# dcdc_0501.net
KiCad netlist of a schematic drawn in EAGLE
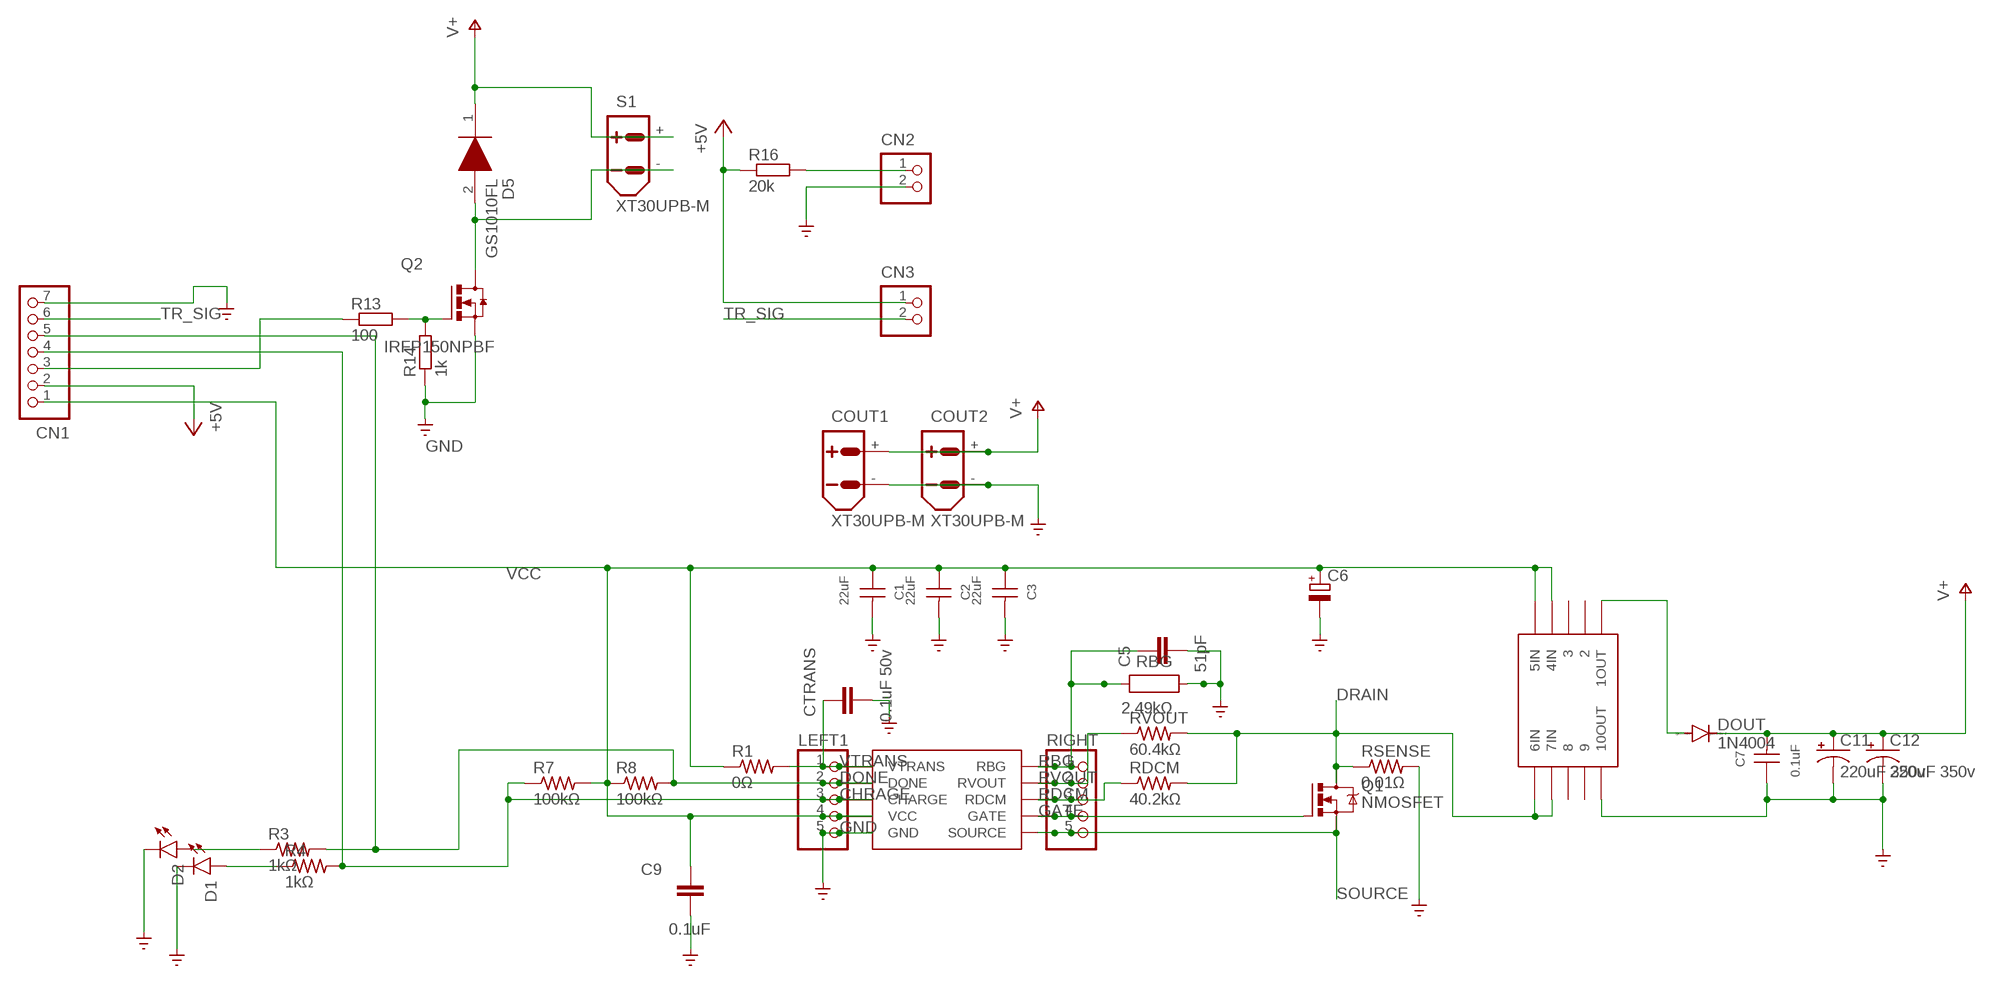
[diagram p0: schematic, sheet 1]

(export (version "E")
  (design (tool "Eeschema 10.0.6"))
  (components
    (comp (ref "C1")
      (value "22uF")
      (footprint "eagle-import:WCAP-CSGP_1210_H0.95")
      (libsource (lib "eagle-import") (part "WCAP-CSGP_1210_H0.95_25V(DC)_885012009002"))
    )
    (comp (ref "C2")
      (value "22uF")
      (footprint "eagle-import:WCAP-CSGP_1210_H0.95")
      (libsource (lib "eagle-import") (part "WCAP-CSGP_1210_H0.95_25V(DC)_885012009002"))
    )
    (comp (ref "C3")
      (value "22uF")
      (footprint "eagle-import:WCAP-CSGP_1210_H0.95")
      (libsource (lib "eagle-import") (part "WCAP-CSGP_1210_H0.95_25V(DC)_885012009002"))
    )
    (comp (ref "C5")
      (value "51pF")
      (footprint "eagle-import:CAP_0603")
      (fields
        (field (name "DIGIKEY_PART_NUMBER") "399-7814-2-ND")
        (field (name "MANUFACTURER") "KEMET")
        (field (name "MPN") "C0603C100C5GACTU")
        (field (name "CREATED_BY") "PCBLayout.com")
      )
      (libsource (lib "eagle-import") (part "C0603C100C5GACTU"))
    )
    (comp (ref "C6")
      (value "CPOL-EUTT2D6")
      (footprint "eagle-import:TT2D6")
      (libsource (lib "eagle-import") (part "CPOL-EUTT2D6"))
    )
    (comp (ref "C7")
      (value "0.1uF")
      (footprint "eagle-import:WCAP-CSGP_1812_H1.25")
      (libsource (lib "eagle-import") (part "WCAP-CSGP_1812_H1.25_16V(DC)_885012010001"))
    )
    (comp (ref "C9")
      (value "0.1uF")
      (footprint "eagle-import:CAP_0603")
      (fields
        (field (name "DIGIKEY_PART_NUMBER") "399-7814-2-ND")
        (field (name "MANUFACTURER") "KEMET")
        (field (name "MPN") "C0603C100C5GACTU")
        (field (name "CREATED_BY") "PCBLayout.com")
      )
      (libsource (lib "eagle-import") (part "C0603C100C5GACTU"))
    )
    (comp (ref "C11")
      (value "220uF 350v")
      (footprint "eagle-import:E7,5-18")
      (libsource (lib "eagle-import") (part "CAPACITOR-PE7.5-18"))
    )
    (comp (ref "C12")
      (value "220uF 350v")
      (footprint "eagle-import:E7,5-18")
      (libsource (lib "eagle-import") (part "CAPACITOR-PE7.5-18"))
    )
    (comp (ref "CN1")
      (value "B7B-XH-A")
      (footprint "eagle-import:B7B-XH-A")
      (libsource (lib "eagle-import") (part "B7B-XH-A"))
    )
    (comp (ref "CN2")
      (value "B2B-XH-A")
      (footprint "eagle-import:B2B-XH-A")
      (libsource (lib "eagle-import") (part "B2B-XH-A"))
    )
    (comp (ref "CN3")
      (value "B2B-XH-A")
      (footprint "eagle-import:B2B-XH-A")
      (libsource (lib "eagle-import") (part "B2B-XH-A"))
    )
    (comp (ref "COUT1")
      (value "XT30UPB-M")
      (footprint "eagle-import:XT30UPB-M")
      (libsource (lib "eagle-import") (part "XT30UPB-M"))
    )
    (comp (ref "COUT2")
      (value "XT30UPB-M")
      (footprint "eagle-import:XT30UPB-M")
      (libsource (lib "eagle-import") (part "XT30UPB-M"))
    )
    (comp (ref "CTRANS")
      (value "0.1uF 50v")
      (footprint "eagle-import:CAP_1206")
      (fields
        (field (name "DIGIKEY_PART_NUMBER") "GRM31CR60J107ME39L")
        (field (name "MANUFACTURER") "Murata Electronics North America")
        (field (name "CREATED_BY") "PCBLayout.com")
      )
      (libsource (lib "eagle-import") (part "GRM31CR60J107ME39L"))
    )
    (comp (ref "D1")
      (value "LED_RADIALWHITE")
      (footprint "eagle-import:LEDRD254W60D565H860B_W")
      (libsource (lib "eagle-import") (part "LED_RADIALWHITE"))
    )
    (comp (ref "D2")
      (value "LED_RADIALWHITE")
      (footprint "eagle-import:LEDRD254W60D565H860B_W")
      (libsource (lib "eagle-import") (part "LED_RADIALWHITE"))
    )
    (comp (ref "D5")
      (value "GS1010FL")
      (footprint "eagle-import:SODFL3618X110N")
      (libsource (lib "eagle-import") (part "GS1010FL"))
    )
    (comp (ref "DOUT")
      (value "1N4004")
      (footprint "eagle-import:DO41-10")
      (libsource (lib "eagle-import") (part "1N4004"))
    )
    (comp (ref "LEFT1")
      (value "PINHD-1X5")
      (footprint "eagle-import:1X05")
      (libsource (lib "eagle-import") (part "PINHD-1X5"))
    )
    (comp (ref "Q1")
      (value "NMOSFET")
      (footprint "eagle-import:TO220BV")
      (libsource (lib "eagle-import") (part "NMOSFET_TO220_"))
    )
    (comp (ref "Q2")
      (value "IRFP150NPBF")
      (footprint "eagle-import:TO-247AC")
      (fields
        (field (name "DIGIKEY_PART_NUMBER") "IRFP150NPBF-ND")
        (field (name "CREATED_BY") "PCBLayout.com")
      )
      (libsource (lib "eagle-import") (part "IRFP150NPBF"))
    )
    (comp (ref "R1")
      (value "0Ω")
      (footprint "eagle-import:M2012")
      (libsource (lib "eagle-import") (part "R-US_M2012"))
    )
    (comp (ref "R3")
      (value "1kΩ")
      (footprint "eagle-import:RES_0402")
      (fields
        (field (name "DIGIKEY_PART_NUMBER") "311-0.0JRTR-ND")
        (field (name "MANUFACTURER") "Yageo")
        (field (name "MPN") "RC0402JR-070RL")
        (field (name "CREATED_BY") "PCBLayout.com")
      )
      (libsource (lib "eagle-import") (part "RC0402JR-070RL"))
    )
    (comp (ref "R4")
      (value "1kΩ")
      (footprint "eagle-import:RES_0402")
      (fields
        (field (name "DIGIKEY_PART_NUMBER") "311-0.0JRTR-ND")
        (field (name "MANUFACTURER") "Yageo")
        (field (name "MPN") "RC0402JR-070RL")
        (field (name "CREATED_BY") "PCBLayout.com")
      )
      (libsource (lib "eagle-import") (part "RC0402JR-070RL"))
    )
    (comp (ref "R7")
      (value "100kΩ")
      (footprint "eagle-import:R1210")
      (libsource (lib "eagle-import") (part "R-US_R1210"))
    )
    (comp (ref "R8")
      (value "100kΩ")
      (footprint "eagle-import:R1210")
      (libsource (lib "eagle-import") (part "R-US_R1210"))
    )
    (comp (ref "R13")
      (value "100")
      (footprint "eagle-import:R0603")
      (libsource (lib "eagle-import") (part "R-EU_R0603"))
    )
    (comp (ref "R14")
      (value "1k")
      (footprint "eagle-import:R0603")
      (libsource (lib "eagle-import") (part "R-EU_R0603"))
    )
    (comp (ref "R16")
      (value "20k")
      (footprint "eagle-import:R0603")
      (libsource (lib "eagle-import") (part "R-EU_R0603"))
    )
    (comp (ref "RBG")
      (value "2.49kΩ")
      (footprint "eagle-import:WRIS_PSMC_2512_6.3X3.1X0.51X1.1(LXWXHXPW)")
      (libsource (lib "eagle-import") (part "WRIS-PSMC_2512_6.3X3.1X0.51X1.1_580070763005"))
    )
    (comp (ref "RDCM")
      (value "40.2kΩ")
      (footprint "eagle-import:RES_0805")
      (fields
        (field (name "DIGIKEY_PART_NUMBER") "541-0.0ATR-ND")
        (field (name "MANUFACTURER") "Vishay Dale")
        (field (name "MPN") "CRCW08050000Z0EA")
        (field (name "CREATED_BY") "PCBLayout.com")
      )
      (libsource (lib "eagle-import") (part "CRCW08050000Z0EA"))
    )
    (comp (ref "RIGHT")
      (value "PINHD-1X5")
      (footprint "eagle-import:1X05")
      (libsource (lib "eagle-import") (part "PINHD-1X5"))
    )
    (comp (ref "RSENSE")
      (value "0.01Ω")
      (footprint "eagle-import:RES_1206")
      (fields
        (field (name "DIGIKEY_PART_NUMBER") "WSLP-.05TR-ND")
        (field (name "MANUFACTURER") "Vishay Dale")
        (field (name "MPN") "WSLP1206R0500FEA")
        (field (name "CREATED_BY") "PCBLayout.com")
      )
      (libsource (lib "eagle-import") (part "WSLP1206R0500FEA"))
    )
    (comp (ref "RVOUT")
      (value "60.4kΩ")
      (footprint "eagle-import:RES_0805")
      (fields
        (field (name "DIGIKEY_PART_NUMBER") "541-0.0ATR-ND")
        (field (name "MANUFACTURER") "Vishay Dale")
        (field (name "MPN") "CRCW08050000Z0EA")
        (field (name "CREATED_BY") "PCBLayout.com")
      )
      (libsource (lib "eagle-import") (part "CRCW08050000Z0EA"))
    )
    (comp (ref "S1")
      (value "XT30UPB-M")
      (footprint "eagle-import:XT30UPB-M")
      (libsource (lib "eagle-import") (part "XT30UPB-M"))
    )
    (comp (ref "U$1")
      (value "LT3750_2")
      (footprint "eagle-import:LT3750_2")
      (libsource (lib "eagle-import") (part "LT3750_2"))
    )
    (comp (ref "U$2")
      (value "32052")
      (footprint "eagle-import:32052")
      (libsource (lib "eagle-import") (part "32052"))
    )
  )
  (nets
    (net (code "1") (name "+5V") (class "Default")
      (node (ref "CN1") (pin "2") (pinfunction "2_2") (pintype "passive"))
      (node (ref "CN3") (pin "1") (pinfunction "1_1") (pintype "passive"))
      (node (ref "R16") (pin "1") (pinfunction "1_1") (pintype "passive"))
    )
    (net (code "2") (name "/CHRAGE") (class "Default")
      (node (ref "CN1") (pin "4") (pinfunction "4_4") (pintype "passive"))
      (node (ref "LEFT1") (pin "3") (pinfunction "3_3") (pintype "passive"))
      (node (ref "R4") (pin "2") (pinfunction "2_2") (pintype "passive"))
      (node (ref "R7") (pin "1") (pinfunction "1_1") (pintype "passive"))
      (node (ref "U$1") (pin "CHARGE") (pinfunction "CHARGE_CHARGE") (pintype "bidirectional"))
    )
    (net (code "3") (name "/DONE") (class "Default")
      (node (ref "CN1") (pin "5") (pinfunction "5_5") (pintype "passive"))
      (node (ref "LEFT1") (pin "2") (pinfunction "2_2") (pintype "passive"))
      (node (ref "R3") (pin "2") (pinfunction "2_2") (pintype "passive"))
      (node (ref "R8") (pin "2") (pinfunction "2_2") (pintype "passive"))
      (node (ref "U$1") (pin "DONE") (pinfunction "DONE_DONE") (pintype "bidirectional"))
    )
    (net (code "4") (name "/DRAIN") (class "Default")
      (node (ref "Q1") (pin "D") (pinfunction "D_D") (pintype "passive"))
      (node (ref "RDCM") (pin "2") (pinfunction "2_2") (pintype "passive"))
      (node (ref "RSENSE") (pin "1") (pinfunction "1_1") (pintype "passive"))
      (node (ref "RVOUT") (pin "2") (pinfunction "2_2") (pintype "passive"))
      (node (ref "U$2") (pin "6IN") (pinfunction "6IN_6IN") (pintype "bidirectional"))
      (node (ref "U$2") (pin "7IN") (pinfunction "7IN_7IN") (pintype "bidirectional"))
    )
    (net (code "5") (name "/GATE") (class "Default")
      (node (ref "Q1") (pin "G") (pinfunction "G_G") (pintype "passive"))
      (node (ref "RIGHT") (pin "4") (pinfunction "4_4") (pintype "passive"))
      (node (ref "U$1") (pin "GATE") (pinfunction "GATE_GATE") (pintype "bidirectional"))
    )
    (net (code "6") (name "/RBG") (class "Default")
      (node (ref "C5") (pin "1") (pinfunction "1_1") (pintype "passive"))
      (node (ref "RBG") (pin "1") (pinfunction "1_1") (pintype "passive"))
      (node (ref "RIGHT") (pin "1") (pinfunction "1_1") (pintype "passive"))
      (node (ref "U$1") (pin "RBG") (pinfunction "RBG_RBG") (pintype "bidirectional"))
    )
    (net (code "7") (name "/RDCM") (class "Default")
      (node (ref "RDCM") (pin "1") (pinfunction "1_1") (pintype "passive"))
      (node (ref "RIGHT") (pin "3") (pinfunction "3_3") (pintype "passive"))
      (node (ref "U$1") (pin "RDCM") (pinfunction "RDCM_RDCM") (pintype "bidirectional"))
    )
    (net (code "8") (name "/RVOUT") (class "Default")
      (node (ref "RIGHT") (pin "2") (pinfunction "2_2") (pintype "passive"))
      (node (ref "RVOUT") (pin "1") (pinfunction "1_1") (pintype "passive"))
      (node (ref "U$1") (pin "RVOUT") (pinfunction "RVOUT_RVOUT") (pintype "bidirectional"))
    )
    (net (code "9") (name "/SOURCE") (class "Default")
      (node (ref "Q1") (pin "S") (pinfunction "S_S") (pintype "passive"))
      (node (ref "RIGHT") (pin "5") (pinfunction "5_5") (pintype "passive"))
      (node (ref "U$1") (pin "SOURCE") (pinfunction "SOURCE_SOURCE") (pintype "bidirectional"))
    )
    (net (code "10") (name "/TR_SIG") (class "Default")
      (node (ref "CN1") (pin "6") (pinfunction "6_6") (pintype "passive"))
      (node (ref "CN3") (pin "2") (pinfunction "2_2") (pintype "passive"))
    )
    (net (code "11") (name "/VCC") (class "Default")
      (node (ref "C1") (pin "1") (pinfunction "1_1") (pintype "passive"))
      (node (ref "C2") (pin "1") (pinfunction "1_1") (pintype "passive"))
      (node (ref "C3") (pin "1") (pinfunction "1_1") (pintype "passive"))
      (node (ref "C6") (pin "+") (pinfunction "+_+") (pintype "passive"))
      (node (ref "C9") (pin "1") (pinfunction "1_1") (pintype "passive"))
      (node (ref "CN1") (pin "1") (pinfunction "1_1") (pintype "passive"))
      (node (ref "LEFT1") (pin "4") (pinfunction "4_4") (pintype "passive"))
      (node (ref "R1") (pin "1") (pinfunction "1_1") (pintype "passive"))
      (node (ref "R7") (pin "2") (pinfunction "2_2") (pintype "passive"))
      (node (ref "R8") (pin "1") (pinfunction "1_1") (pintype "passive"))
      (node (ref "U$1") (pin "VCC") (pinfunction "VCC_VCC") (pintype "bidirectional"))
      (node (ref "U$2") (pin "4IN") (pinfunction "4IN_4IN") (pintype "bidirectional"))
      (node (ref "U$2") (pin "5IN") (pinfunction "5IN_5IN") (pintype "bidirectional"))
    )
    (net (code "12") (name "/VTRANS") (class "Default")
      (node (ref "CTRANS") (pin "1") (pinfunction "1_1") (pintype "passive"))
      (node (ref "LEFT1") (pin "1") (pinfunction "1_1") (pintype "passive"))
      (node (ref "R1") (pin "2") (pinfunction "2_2") (pintype "passive"))
      (node (ref "U$1") (pin "VTRANS") (pinfunction "VTRANS_VTRANS") (pintype "bidirectional"))
    )
    (net (code "13") (name "Net-(CN1-Pad3)") (class "Default")
      (node (ref "CN1") (pin "3") (pinfunction "3_3") (pintype "passive"))
      (node (ref "R13") (pin "1") (pinfunction "1_1") (pintype "passive"))
    )
    (net (code "14") (name "Net-(CN2-Pad1)") (class "Default")
      (node (ref "CN2") (pin "1") (pinfunction "1_1") (pintype "passive"))
      (node (ref "R16") (pin "2") (pinfunction "2_2") (pintype "passive"))
    )
    (net (code "15") (name "Net-(D1-PadA)") (class "Default")
      (node (ref "D1") (pin "A") (pinfunction "A_A") (pintype "passive"))
      (node (ref "R4") (pin "1") (pinfunction "1_1") (pintype "passive"))
    )
    (net (code "16") (name "Net-(D2-PadA)") (class "Default")
      (node (ref "D2") (pin "A") (pinfunction "A_A") (pintype "passive"))
      (node (ref "R3") (pin "1") (pinfunction "1_1") (pintype "passive"))
    )
    (net (code "17") (name "Net-(D5-A)") (class "Default")
      (node (ref "D5") (pin "2") (pinfunction "A_2") (pintype "bidirectional"))
      (node (ref "Q2") (pin "D") (pinfunction "D_D") (pintype "passive"))
      (node (ref "S1") (pin "-") (pinfunction "-_-") (pintype "power_in"))
    )
    (net (code "18") (name "Net-(DOUT-PadA)") (class "Default")
      (node (ref "DOUT") (pin "A") (pinfunction "A_A") (pintype "passive"))
      (node (ref "U$2") (pin "1OUT") (pinfunction "1OUT_1OUT") (pintype "bidirectional"))
    )
    (net (code "19") (name "Net-(Q2-PadG)") (class "Default")
      (node (ref "Q2") (pin "G") (pinfunction "G_G") (pintype "passive"))
      (node (ref "R13") (pin "2") (pinfunction "2_2") (pintype "passive"))
      (node (ref "R14") (pin "2") (pinfunction "2_2") (pintype "passive"))
    )
    (net (code "20") (name "SUPPLY0_GND_") (class "Default")
      (node (ref "C1") (pin "2") (pinfunction "2_2") (pintype "passive"))
      (node (ref "C11") (pin "-") (pinfunction "-_-") (pintype "passive"))
      (node (ref "C12") (pin "-") (pinfunction "-_-") (pintype "passive"))
      (node (ref "C2") (pin "2") (pinfunction "2_2") (pintype "passive"))
      (node (ref "C3") (pin "2") (pinfunction "2_2") (pintype "passive"))
      (node (ref "C5") (pin "2") (pinfunction "2_2") (pintype "passive"))
      (node (ref "C6") (pin "-") (pinfunction "-_-") (pintype "passive"))
      (node (ref "C7") (pin "1") (pinfunction "1_1") (pintype "passive"))
      (node (ref "C9") (pin "2") (pinfunction "2_2") (pintype "passive"))
      (node (ref "CN1") (pin "7") (pinfunction "7_7") (pintype "passive"))
      (node (ref "CN2") (pin "2") (pinfunction "2_2") (pintype "passive"))
      (node (ref "COUT1") (pin "-") (pinfunction "-_-") (pintype "power_in"))
      (node (ref "COUT2") (pin "-") (pinfunction "-_-") (pintype "power_in"))
      (node (ref "CTRANS") (pin "2") (pinfunction "2_2") (pintype "passive"))
      (node (ref "D1") (pin "C") (pinfunction "C_C") (pintype "passive"))
      (node (ref "D2") (pin "C") (pinfunction "C_C") (pintype "passive"))
      (node (ref "LEFT1") (pin "5") (pinfunction "5_5") (pintype "passive"))
      (node (ref "Q2") (pin "S") (pinfunction "S_S") (pintype "passive"))
      (node (ref "R14") (pin "1") (pinfunction "1_1") (pintype "passive"))
      (node (ref "RBG") (pin "2") (pinfunction "2_2") (pintype "passive"))
      (node (ref "RSENSE") (pin "2") (pinfunction "2_2") (pintype "passive"))
      (node (ref "U$1") (pin "GND") (pinfunction "GND_GND") (pintype "bidirectional"))
      (node (ref "U$2") (pin "10OUT") (pinfunction "10OUT_10OUT") (pintype "bidirectional"))
    )
    (net (code "21") (name "V+") (class "Default")
      (node (ref "C11") (pin "+") (pinfunction "+_+") (pintype "passive"))
      (node (ref "C12") (pin "+") (pinfunction "+_+") (pintype "passive"))
      (node (ref "C7") (pin "2") (pinfunction "2_2") (pintype "passive"))
      (node (ref "COUT1") (pin "+") (pinfunction "+_+") (pintype "power_in"))
      (node (ref "COUT2") (pin "+") (pinfunction "+_+") (pintype "power_in"))
      (node (ref "D5") (pin "1") (pinfunction "K_1") (pintype "bidirectional"))
      (node (ref "DOUT") (pin "C") (pinfunction "C_C") (pintype "passive"))
      (node (ref "S1") (pin "+") (pinfunction "+_+") (pintype "power_in"))
    )
    (net (code "22") (name "unconnected-(U$2-Pad2)") (class "Default")
      (node (ref "U$2") (pin "2") (pinfunction "2_2") (pintype "bidirectional"))
    )
    (net (code "23") (name "unconnected-(U$2-Pad3)") (class "Default")
      (node (ref "U$2") (pin "3") (pinfunction "3_3") (pintype "bidirectional"))
    )
    (net (code "24") (name "unconnected-(U$2-Pad8)") (class "Default")
      (node (ref "U$2") (pin "8") (pinfunction "8_8") (pintype "bidirectional"))
    )
    (net (code "25") (name "unconnected-(U$2-Pad9)") (class "Default")
      (node (ref "U$2") (pin "9") (pinfunction "9_9") (pintype "bidirectional"))
    )
  )
)
